# USB_Sheet_ATmega8U2-MU.net
KiCad netlist of a schematic drawn in Altium Designer
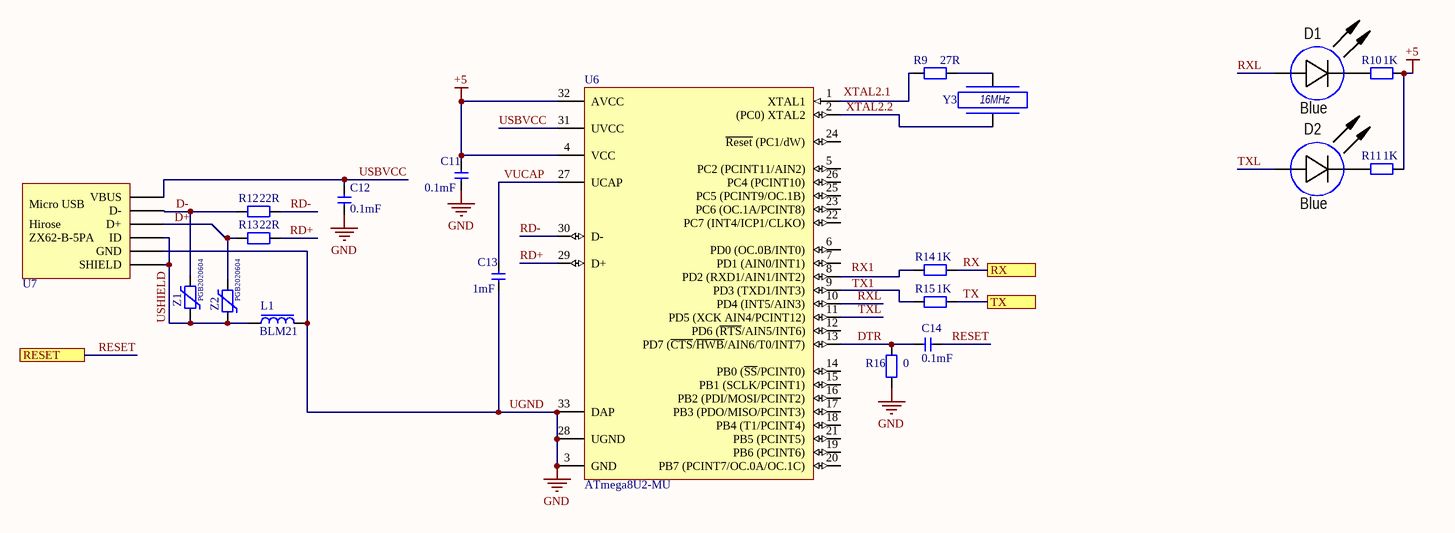
[diagram p0: USB Sheet (ATmega8U2-MU).SchDoc]

(export (version "E")
  (design (tool "Eeschema 10.0.6"))
  (components
    (comp (ref "C11")
      (value "0.1mF")
      (footprint "cap0603")
      (libsource (lib "AlexChistiakov") (part "Cap SMD"))
    )
    (comp (ref "C12")
      (value "0.1mF")
      (footprint "cap0603")
      (libsource (lib "AlexChistiakov") (part "Cap SMD"))
    )
    (comp (ref "C13") (value "1mF") (footprint "cap0603") (libsource (lib "AlexChistiakov") (part "Cap SMD")))
    (comp (ref "C14")
      (value "0.1mF")
      (footprint "cap0603")
      (libsource (lib "AlexChistiakov") (part "Cap SMD"))
    )
    (comp (ref "D1") (value "Blue") (footprint "standard:CH0805LB") (libsource (lib "Discrete") (part "LED")))
    (comp (ref "D2") (value "Blue") (footprint "standard:CH0805LB") (libsource (lib "Discrete") (part "LED")))
    (comp (ref "L1")
      (value "BLM21")
      (footprint "res0805")
      (libsource (lib "AlexChistiakov") (part "Drossel"))
    )
    (comp (ref "R9")
      (value "27R")
      (footprint "res0603")
      (libsource (lib "AlexChistiakov") (part "Resistor SMD"))
    )
    (comp (ref "R10")
      (value "1K")
      (footprint "res0603")
      (libsource (lib "AlexChistiakov") (part "Resistor SMD"))
    )
    (comp (ref "R11")
      (value "1K")
      (footprint "res0603")
      (libsource (lib "AlexChistiakov") (part "Resistor SMD"))
    )
    (comp (ref "R12")
      (value "22R")
      (footprint "res0603")
      (libsource (lib "AlexChistiakov") (part "Resistor SMD"))
    )
    (comp (ref "R13")
      (value "22R")
      (footprint "res0603")
      (libsource (lib "AlexChistiakov") (part "Resistor SMD"))
    )
    (comp (ref "R14")
      (value "1K")
      (footprint "res0603")
      (libsource (lib "AlexChistiakov") (part "Resistor SMD"))
    )
    (comp (ref "R15")
      (value "1K")
      (footprint "res0603")
      (libsource (lib "AlexChistiakov") (part "Resistor SMD"))
    )
    (comp (ref "R16")
      (value "0")
      (footprint "res0603")
      (libsource (lib "AlexChistiakov") (part "Resistor SMD"))
    )
    (comp (ref "U6")
      (value "ATmega8U2-MU")
      (footprint "32PG_N")
      (fields (field (name "PUBLISHER") "Altium Limited"))
      (libsource (lib "Atmel Microcontroller 8-Bit megaAVR") (part "ATmega8U2-MU"))
    )
    (comp (ref "U7")
      (value "ZX62-B-5PA")
      (footprint "ZX62-B-5PA")
      (libsource (lib "AlexChistiakov") (part "ZX62-B-5PA"))
    )
    (comp (ref "Y3")
      (value "16MHz")
      (footprint "QSMD5.0x3.2x1.0")
      (description "Кварцевый резонатор")
      (libsource (lib "TarabusLib_KOR") (part "Crystal"))
    )
    (comp (ref "Z1")
      (value "PGB2020604")
      (footprint "res0603")
      (libsource (lib "AlexChistiakov") (part "Varistor"))
    )
    (comp (ref "Z2")
      (value "PGB2020604")
      (footprint "res0603")
      (libsource (lib "AlexChistiakov") (part "Varistor"))
    )
  )
  (nets
    (net (code "1") (name "+5") (class "Default")
      (node (ref "C11") (pin "2") (pinfunction "2_2") (pintype "passive"))
      (node (ref "R10") (pin "2") (pinfunction "2_2") (pintype "passive"))
      (node (ref "R11") (pin "2") (pinfunction "2_2") (pintype "passive"))
      (node (ref "U6") (pin "32") (pinfunction "AVCC_32") (pintype "power_in"))
      (node (ref "U6") (pin "4") (pinfunction "VCC_4") (pintype "power_in"))
    )
    (net (code "3") (name "/D-") (class "Default")
      (node (ref "R12") (pin "1") (pinfunction "1_1") (pintype "passive"))
      (node (ref "U7") (pin "2") (pinfunction "D-_2") (pintype "passive"))
      (node (ref "Z1") (pin "2") (pinfunction "2_2") (pintype "passive"))
    )
    (net (code "4") (name "/DTR") (class "Default")
      (node (ref "C14") (pin "1") (pinfunction "1_1") (pintype "passive"))
      (node (ref "R16") (pin "2") (pinfunction "2_2") (pintype "passive"))
      (node (ref "U6") (pin "13") (pinfunction "PD7_(~{CTS}/~{HWB}/AIN6/T0/INT7)_13") (pintype "bidirectional"))
    )
    (net (code "5") (name "/RD+") (class "Default")
      (node (ref "R13") (pin "2") (pinfunction "2_2") (pintype "passive"))
      (node (ref "U6") (pin "29") (pinfunction "D+_29") (pintype "bidirectional"))
    )
    (net (code "6") (name "/RD-") (class "Default")
      (node (ref "R12") (pin "2") (pinfunction "2_2") (pintype "passive"))
      (node (ref "U6") (pin "30") (pinfunction "D-_30") (pintype "bidirectional"))
    )
    (net (code "7") (name "/RESET") (class "Default")
      (node (ref "C14") (pin "2") (pinfunction "2_2") (pintype "passive"))
    )
    (net (code "8") (name "/RX") (class "Default")
      (node (ref "R14") (pin "2") (pinfunction "2_2") (pintype "passive"))
    )
    (net (code "10") (name "/RXL") (class "Default")
      (node (ref "D1") (pin "1") (pinfunction "A_1") (pintype "passive"))
      (node (ref "U6") (pin "10") (pinfunction "PD4_(INT5/AIN3)_10") (pintype "bidirectional"))
    )
    (net (code "11") (name "/TX") (class "Default")
      (node (ref "R15") (pin "2") (pinfunction "2_2") (pintype "passive"))
    )
    (net (code "13") (name "/TXL") (class "Default")
      (node (ref "D2") (pin "1") (pinfunction "A_1") (pintype "passive"))
      (node (ref "U6") (pin "11") (pinfunction "PD5_(XCK_AIN4/PCINT12)_11") (pintype "bidirectional"))
    )
    (net (code "14") (name "/USBVCC") (class "Default")
      (node (ref "C12") (pin "2") (pinfunction "2_2") (pintype "passive"))
      (node (ref "U6") (pin "31") (pinfunction "UVCC_31") (pintype "power_in"))
      (node (ref "U7") (pin "1") (pinfunction "VBUS_1") (pintype "passive"))
    )
    (net (code "15") (name "/USHIELD") (class "Default")
      (node (ref "L1") (pin "1") (pinfunction "1_1") (pintype "passive"))
      (node (ref "U7") (pin "4") (pinfunction "ID_4") (pintype "passive"))
      (node (ref "U7") (pin "6") (pinfunction "SHIELD_6") (pintype "passive"))
      (node (ref "Z1") (pin "1") (pinfunction "1_1") (pintype "passive"))
      (node (ref "Z2") (pin "1") (pinfunction "1_1") (pintype "passive"))
    )
    (net (code "16") (name "/VUCAP") (class "Default")
      (node (ref "C13") (pin "2") (pinfunction "2_2") (pintype "passive"))
      (node (ref "U6") (pin "27") (pinfunction "UCAP_27") (pintype "power_in"))
    )
    (net (code "18") (name "/XTAL2.2") (class "Default")
      (node (ref "U6") (pin "2") (pinfunction "(PC0)_XTAL2_2") (pintype "bidirectional"))
      (node (ref "Y3") (pin "1") (pinfunction "1_1") (pintype "passive"))
    )
    (net (code "19") (name "GND") (class "Default")
      (node (ref "C11") (pin "1") (pinfunction "1_1") (pintype "passive"))
      (node (ref "C12") (pin "1") (pinfunction "1_1") (pintype "passive"))
      (node (ref "C13") (pin "1") (pinfunction "1_1") (pintype "passive"))
      (node (ref "L1") (pin "2") (pinfunction "2_2") (pintype "passive"))
      (node (ref "R16") (pin "1") (pinfunction "1_1") (pintype "passive"))
      (node (ref "U6") (pin "28") (pinfunction "UGND_28") (pintype "power_in"))
      (node (ref "U6") (pin "3") (pinfunction "GND_3") (pintype "power_in"))
      (node (ref "U6") (pin "33") (pinfunction "DAP_33") (pintype "power_in"))
      (node (ref "U7") (pin "5") (pinfunction "GND_5") (pintype "passive"))
    )
    (net (code "20") (name "Net-(D1-C)") (class "Default")
      (node (ref "D1") (pin "2") (pinfunction "C_2") (pintype "passive"))
      (node (ref "R10") (pin "1") (pinfunction "1_1") (pintype "passive"))
    )
    (net (code "21") (name "Net-(D2-C)") (class "Default")
      (node (ref "D2") (pin "2") (pinfunction "C_2") (pintype "passive"))
      (node (ref "R11") (pin "1") (pinfunction "1_1") (pintype "passive"))
    )
    (net (code "22") (name "Net-(R9-Pad2)") (class "Default")
      (node (ref "R9") (pin "2") (pinfunction "2_2") (pintype "passive"))
      (node (ref "Y3") (pin "2") (pinfunction "2_2") (pintype "passive"))
    )
    (net (code "23") (name "Net-(U6-PD2_(RXD1{slash}AIN1{slash}INT2))") (class "Default")
      (node (ref "R14") (pin "1") (pinfunction "1_1") (pintype "passive"))
      (node (ref "U6") (pin "8") (pinfunction "PD2_(RXD1/AIN1/INT2)_8") (pintype "bidirectional"))
    )
    (net (code "24") (name "Net-(U6-PD3_(TXD1{slash}INT3))") (class "Default")
      (node (ref "R15") (pin "1") (pinfunction "1_1") (pintype "passive"))
      (node (ref "U6") (pin "9") (pinfunction "PD3_(TXD1/INT3)_9") (pintype "bidirectional"))
    )
    (net (code "25") (name "Net-(U6-XTAL1)") (class "Default")
      (node (ref "R9") (pin "1") (pinfunction "1_1") (pintype "passive"))
      (node (ref "U6") (pin "1") (pinfunction "XTAL1_1") (pintype "input"))
    )
    (net (code "26") (name "Net-(U7-D+)") (class "Default")
      (node (ref "R13") (pin "1") (pinfunction "1_1") (pintype "passive"))
      (node (ref "U7") (pin "3") (pinfunction "D+_3") (pintype "passive"))
      (node (ref "Z2") (pin "2") (pinfunction "2_2") (pintype "passive"))
    )
    (net (code "27") (name "unconnected-(U6-PB0_(~{SS}{slash}PCINT0)-Pad14)") (class "Default")
      (node (ref "U6") (pin "14") (pinfunction "PB0_(~{SS}/PCINT0)_14") (pintype "bidirectional"))
    )
    (net (code "28") (name "unconnected-(U6-PB1_(SCLK{slash}PCINT1)-Pad15)") (class "Default")
      (node (ref "U6") (pin "15") (pinfunction "PB1_(SCLK/PCINT1)_15") (pintype "bidirectional"))
    )
    (net (code "29") (name "unconnected-(U6-PB2_(PDI{slash}MOSI{slash}PCINT2)-Pad16)") (class "Default")
      (node (ref "U6") (pin "16") (pinfunction "PB2_(PDI/MOSI/PCINT2)_16") (pintype "bidirectional"))
    )
    (net (code "30") (name "unconnected-(U6-PB3_(PDO{slash}MISO{slash}PCINT3)-Pad17)") (class "Default")
      (node (ref "U6") (pin "17") (pinfunction "PB3_(PDO/MISO/PCINT3)_17") (pintype "bidirectional"))
    )
    (net (code "31") (name "unconnected-(U6-PB4_(T1{slash}PCINT4)-Pad18)") (class "Default")
      (node (ref "U6") (pin "18") (pinfunction "PB4_(T1/PCINT4)_18") (pintype "bidirectional"))
    )
    (net (code "32") (name "unconnected-(U6-PB5_(PCINT5)-Pad21)") (class "Default")
      (node (ref "U6") (pin "21") (pinfunction "PB5_(PCINT5)_21") (pintype "bidirectional"))
    )
    (net (code "33") (name "unconnected-(U6-PB6_(PCINT6)-Pad19)") (class "Default")
      (node (ref "U6") (pin "19") (pinfunction "PB6_(PCINT6)_19") (pintype "bidirectional"))
    )
    (net (code "34") (name "unconnected-(U6-PB7_(PCINT7{slash}OC.0A{slash}OC.1C)-Pad20)") (class "Default")
      (node (ref "U6") (pin "20") (pinfunction "PB7_(PCINT7/OC.0A/OC.1C)_20") (pintype "bidirectional"))
    )
    (net (code "35") (name "unconnected-(U6-PC2_(PCINT11{slash}AIN2)-Pad5)") (class "Default")
      (node (ref "U6") (pin "5") (pinfunction "PC2_(PCINT11/AIN2)_5") (pintype "bidirectional"))
    )
    (net (code "36") (name "unconnected-(U6-PC4_(PCINT10)-Pad26)") (class "Default")
      (node (ref "U6") (pin "26") (pinfunction "PC4_(PCINT10)_26") (pintype "bidirectional"))
    )
    (net (code "37") (name "unconnected-(U6-PC5_(PCINT9{slash}OC.1B)-Pad25)") (class "Default")
      (node (ref "U6") (pin "25") (pinfunction "PC5_(PCINT9/OC.1B)_25") (pintype "bidirectional"))
    )
    (net (code "38") (name "unconnected-(U6-PC6_(OC.1A{slash}PCINT8)-Pad23)") (class "Default")
      (node (ref "U6") (pin "23") (pinfunction "PC6_(OC.1A/PCINT8)_23") (pintype "bidirectional"))
    )
    (net (code "39") (name "unconnected-(U6-PC7_(INT4{slash}ICP1{slash}CLKO)-Pad22)") (class "Default")
      (node (ref "U6") (pin "22") (pinfunction "PC7_(INT4/ICP1/CLKO)_22") (pintype "bidirectional"))
    )
    (net (code "40") (name "unconnected-(U6-PD0_(OC.0B{slash}INT0)-Pad6)") (class "Default")
      (node (ref "U6") (pin "6") (pinfunction "PD0_(OC.0B/INT0)_6") (pintype "bidirectional"))
    )
    (net (code "41") (name "unconnected-(U6-PD1_(AIN0{slash}INT1)-Pad7)") (class "Default")
      (node (ref "U6") (pin "7") (pinfunction "PD1_(AIN0/INT1)_7") (pintype "bidirectional"))
    )
    (net (code "42") (name "unconnected-(U6-PD6_(~{RTS}{slash}AIN5{slash}INT6)-Pad12)") (class "Default")
      (node (ref "U6") (pin "12") (pinfunction "PD6_(~{RTS}/AIN5/INT6)_12") (pintype "bidirectional"))
    )
    (net (code "43") (name "unconnected-(U6-~{Reset}_(PC1{slash}dW)-Pad24)") (class "Default")
      (node (ref "U6") (pin "24") (pinfunction "~{Reset}_(PC1/dW)_24") (pintype "bidirectional"))
    )
  )
)
